# SCH_Trabajo_TEC.net
KiCad netlist of a schematic drawn in EasyEDA
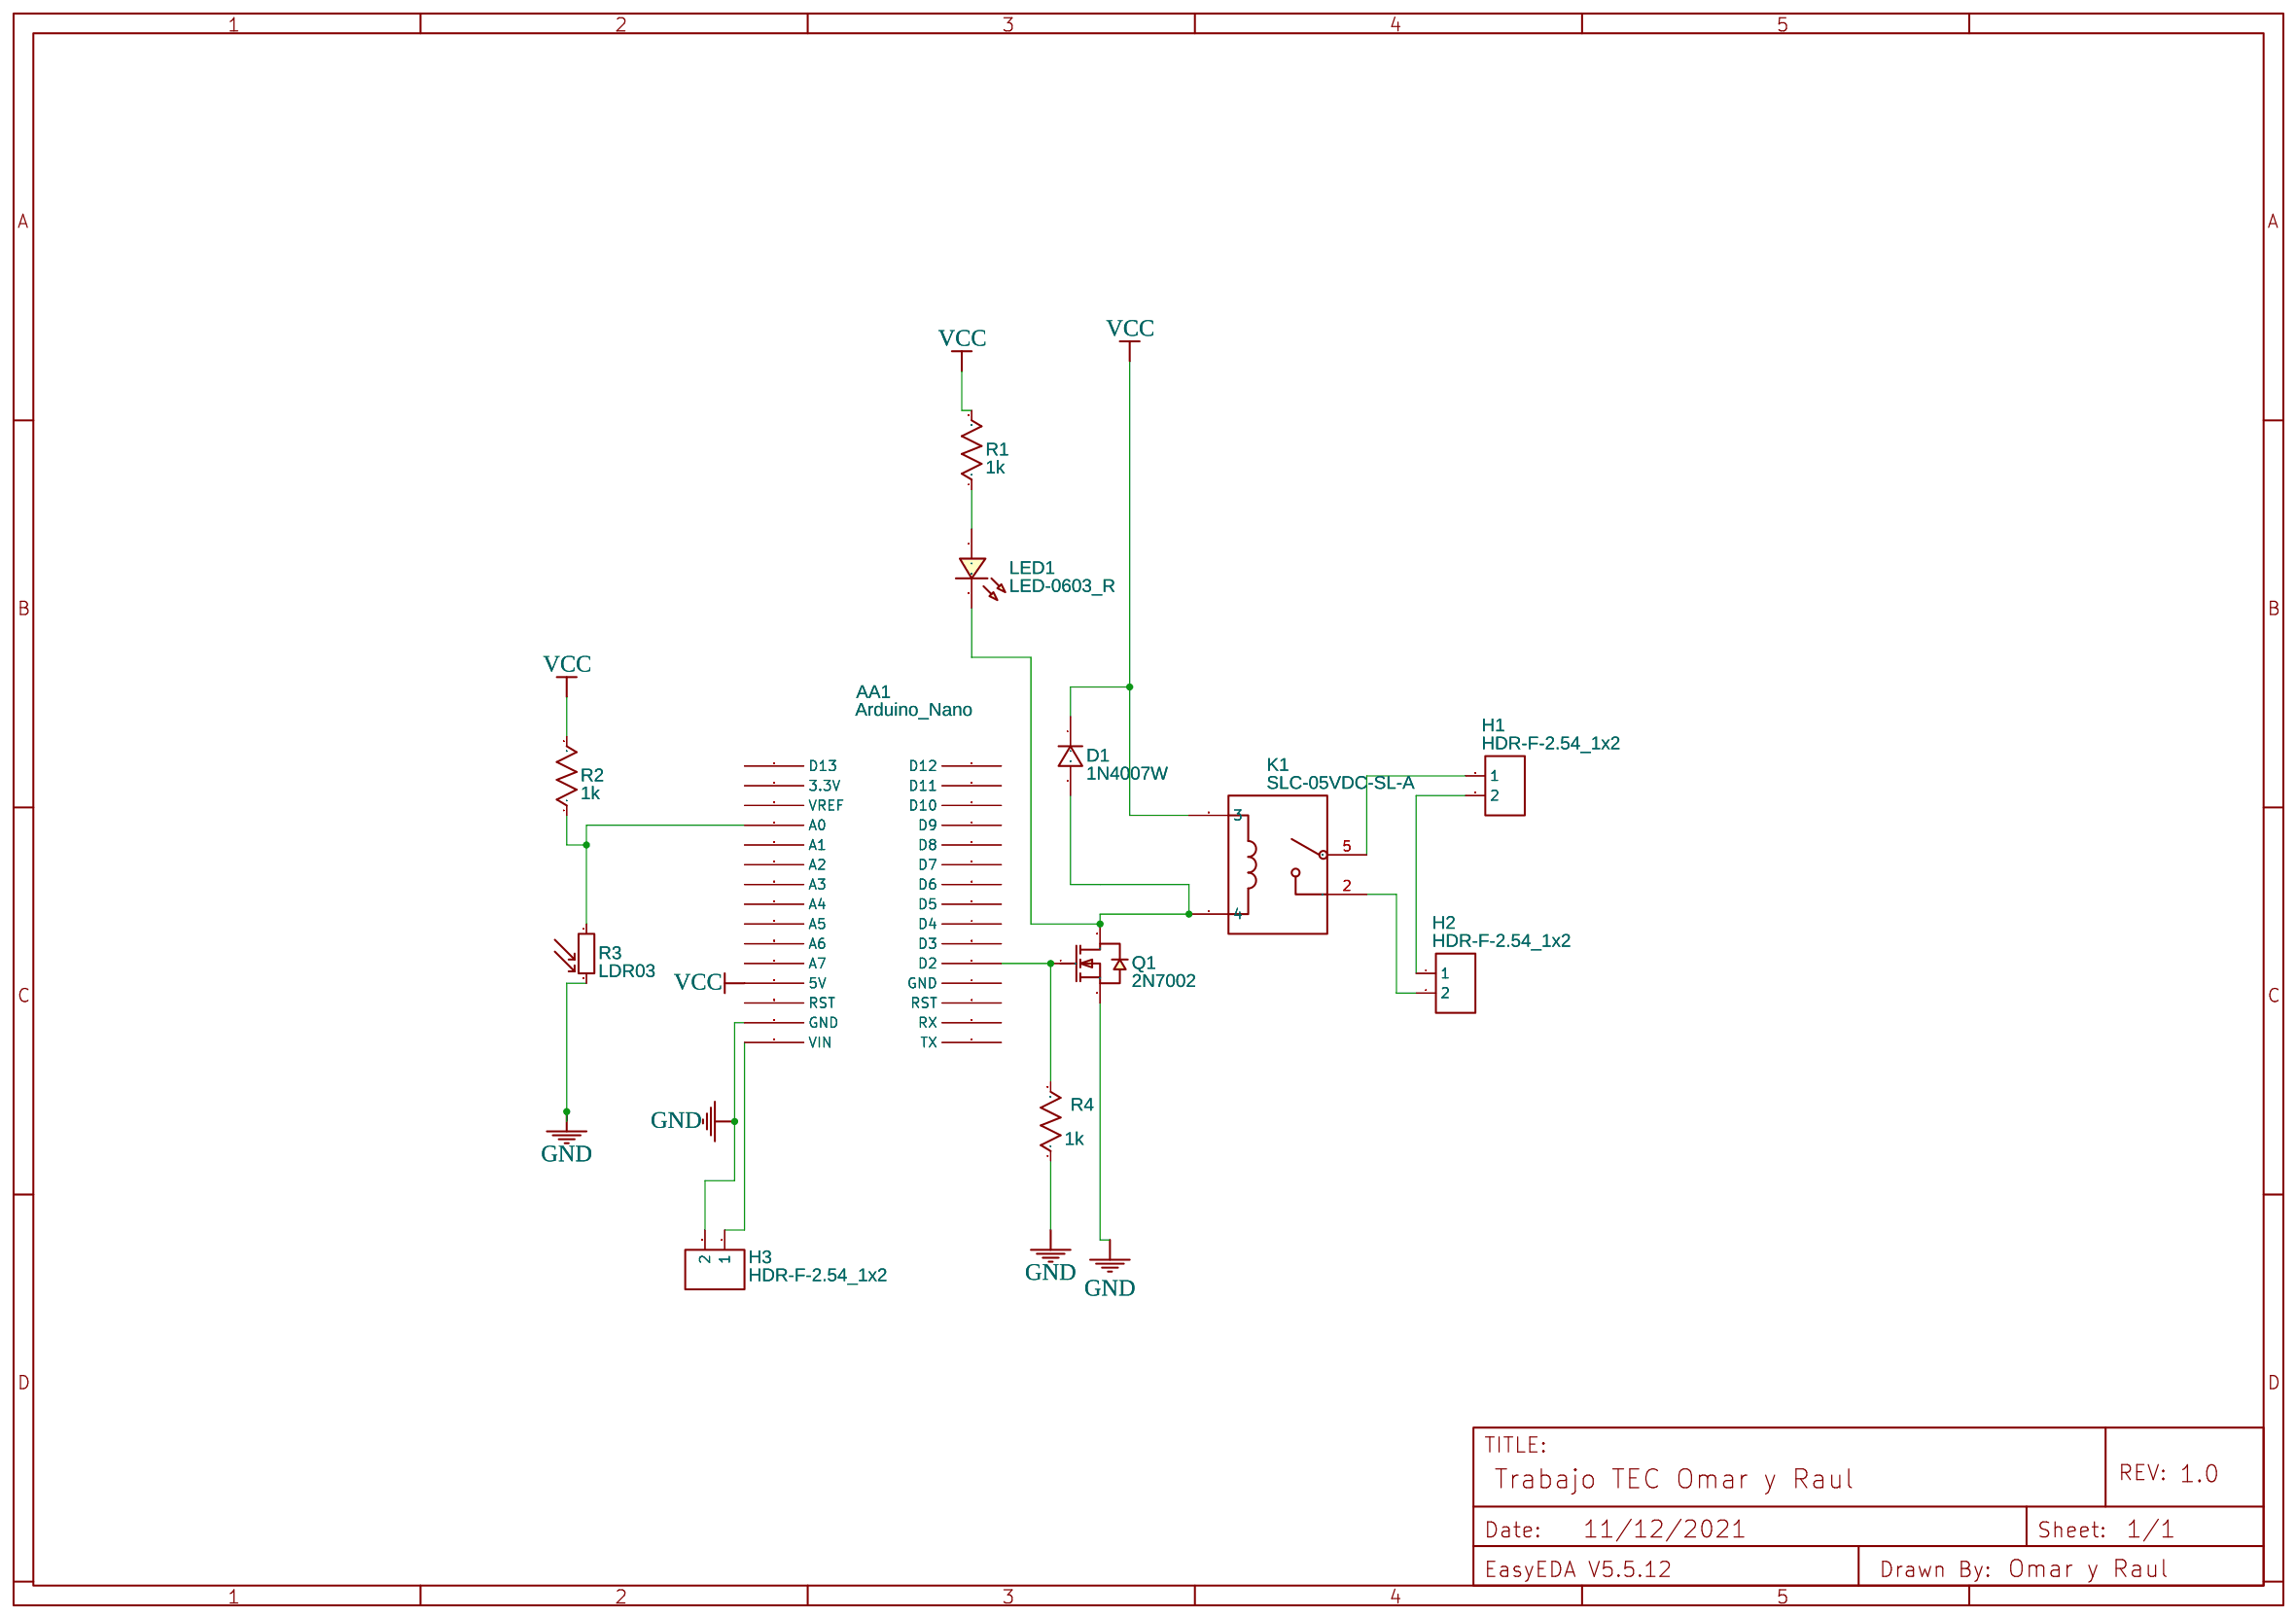
[diagram p0: schematic sheet]

(export (version "E")
  (design (tool "Eeschema 10.0.6"))
  (components
    (comp (ref "AA1")
      (value "Arduino_Nano")
      (fields (field (name "BOM_Manufacturer Part") "Arduino Nano"))
      (libsource (lib "") (part "Unknown_520_-360"))
    )
    (comp (ref "D1")
      (value "1N4007W")
      (fields (field (name "BOM_Supplier Part") "C328592"))
      (libsource (lib "") (part "1N4007W"))
    )
    (comp (ref "H1")
      (value "HDR-F-2.54_1x2")
      (fields (field (name "BOM_Supplier Part") "C49661"))
      (libsource (lib "") (part "HDR-F-2.54_1x2_1"))
    )
    (comp (ref "H2")
      (value "HDR-F-2.54_1x2")
      (fields (field (name "BOM_Supplier Part") "C49661"))
      (libsource (lib "") (part "HDR-F-2.54_1x2_1"))
    )
    (comp (ref "H3")
      (value "HDR-F-2.54_1x2")
      (fields (field (name "BOM_Supplier Part") "C49661"))
      (libsource (lib "") (part "HDR-F-2.54_1x2"))
    )
    (comp (ref "K1")
      (value "SLC-05VDC-SL-A")
      (fields (field (name "BOM_Supplier Part") "C187903"))
      (libsource (lib "") (part "SLC-05VDC-SL-A"))
    )
    (comp (ref "LED1")
      (value "LED-0603_R")
      (fields
        (field (name "BOM_Manufacturer Part") "19-217/R6C-AL1M2VY/3T")
        (field (name "BOM_Supplier Part") "C72044")
      )
      (libsource (lib "") (part "LED-0603_R"))
    )
    (comp (ref "Q1")
      (value "2N7002")
      (fields (field (name "BOM_Manufacturer Part") "2N7002,215") (field (name "BOM_Supplier Part") "C65189"))
      (libsource (lib "") (part "2N7002"))
    )
    (comp (ref "R1") (value "1k") (libsource (lib "") (part "R_0603_US")))
    (comp (ref "R2") (value "1k") (libsource (lib "") (part "R_0603_US")))
    (comp (ref "R3") (value "LDR03") (libsource (lib "") (part "LDR03")))
    (comp (ref "R4") (value "1k") (libsource (lib "") (part "R_0603_US")))
  )
  (nets
    (net (code "1") (name "GND") (class "Default")
      (node (ref "AA1") (pin "29") (pinfunction "GND_29") (pintype "unspecified"))
      (node (ref "H3") (pin "2") (pinfunction "2_2") (pintype "input"))
      (node (ref "Q1") (pin "2") (pinfunction "S_2") (pintype "unspecified"))
      (node (ref "R3") (pin "2") (pintype "unspecified"))
      (node (ref "R4") (pin "1") (pinfunction "1_1") (pintype "unspecified"))
    )
    (net (code "2") (name "Net-(AA1-A0)") (class "Default")
      (node (ref "AA1") (pin "19") (pinfunction "A0_19") (pintype "unspecified"))
      (node (ref "R2") (pin "1") (pinfunction "1_1") (pintype "unspecified"))
      (node (ref "R3") (pin "1") (pintype "unspecified"))
    )
    (net (code "3") (name "Net-(AA1-D2)") (class "Default")
      (node (ref "AA1") (pin "5") (pinfunction "D2_5") (pintype "unspecified"))
      (node (ref "Q1") (pin "1") (pinfunction "G_1") (pintype "unspecified"))
      (node (ref "R4") (pin "2") (pinfunction "2_2") (pintype "unspecified"))
    )
    (net (code "4") (name "Net-(AA1-VIN)") (class "Default")
      (node (ref "AA1") (pin "30") (pinfunction "VIN_30") (pintype "unspecified"))
      (node (ref "H3") (pin "1") (pinfunction "1_1") (pintype "input"))
    )
    (net (code "5") (name "Net-(H1-Pad1)") (class "Default")
      (node (ref "H1") (pin "1") (pinfunction "1_1") (pintype "input"))
      (node (ref "K1") (pin "5") (pinfunction "5_5") (pintype "unspecified"))
    )
    (net (code "6") (name "Net-(H1-Pad2)") (class "Default")
      (node (ref "H1") (pin "2") (pinfunction "2_2") (pintype "input"))
      (node (ref "H2") (pin "1") (pinfunction "1_1") (pintype "input"))
    )
    (net (code "7") (name "Net-(H2-Pad2)") (class "Default")
      (node (ref "H2") (pin "2") (pinfunction "2_2") (pintype "input"))
      (node (ref "K1") (pin "2") (pinfunction "2_2") (pintype "unspecified"))
    )
    (net (code "8") (name "Net-(LED1-Pad1)") (class "Default")
      (node (ref "LED1") (pin "1") (pinfunction "1_1") (pintype "unspecified"))
      (node (ref "R1") (pin "1") (pinfunction "1_1") (pintype "unspecified"))
    )
    (net (code "9") (name "Net-(Q1-D)") (class "Default")
      (node (ref "D1") (pin "2") (pinfunction "2_2") (pintype "unspecified"))
      (node (ref "K1") (pin "4") (pinfunction "4_4") (pintype "unspecified"))
      (node (ref "LED1") (pin "2") (pinfunction "2_2") (pintype "unspecified"))
      (node (ref "Q1") (pin "3") (pinfunction "D_3") (pintype "unspecified"))
    )
    (net (code "10") (name "VCC") (class "Default")
      (node (ref "AA1") (pin "27") (pinfunction "5V_27") (pintype "unspecified"))
      (node (ref "D1") (pin "1") (pinfunction "1_1") (pintype "unspecified"))
      (node (ref "K1") (pin "3") (pinfunction "3_3") (pintype "unspecified"))
      (node (ref "R1") (pin "2") (pinfunction "2_2") (pintype "unspecified"))
      (node (ref "R2") (pin "2") (pinfunction "2_2") (pintype "unspecified"))
    )
    (net (code "11") (name "unconnected-(AA1-3.3V-Pad17)") (class "Default")
      (node (ref "AA1") (pin "17") (pinfunction "3.3V_17") (pintype "unspecified"))
    )
    (net (code "12") (name "unconnected-(AA1-A1-Pad20)") (class "Default")
      (node (ref "AA1") (pin "20") (pinfunction "A1_20") (pintype "unspecified"))
    )
    (net (code "13") (name "unconnected-(AA1-A2-Pad21)") (class "Default")
      (node (ref "AA1") (pin "21") (pinfunction "A2_21") (pintype "unspecified"))
    )
    (net (code "14") (name "unconnected-(AA1-A3-Pad22)") (class "Default")
      (node (ref "AA1") (pin "22") (pinfunction "A3_22") (pintype "unspecified"))
    )
    (net (code "15") (name "unconnected-(AA1-A4-Pad23)") (class "Default")
      (node (ref "AA1") (pin "23") (pinfunction "A4_23") (pintype "unspecified"))
    )
    (net (code "16") (name "unconnected-(AA1-A5-Pad24)") (class "Default")
      (node (ref "AA1") (pin "24") (pinfunction "A5_24") (pintype "unspecified"))
    )
    (net (code "17") (name "unconnected-(AA1-A6-Pad25)") (class "Default")
      (node (ref "AA1") (pin "25") (pinfunction "A6_25") (pintype "unspecified"))
    )
    (net (code "18") (name "unconnected-(AA1-A7-Pad26)") (class "Default")
      (node (ref "AA1") (pin "26") (pinfunction "A7_26") (pintype "unspecified"))
    )
    (net (code "19") (name "unconnected-(AA1-D3-Pad6)") (class "Default")
      (node (ref "AA1") (pin "6") (pinfunction "D3_6") (pintype "unspecified"))
    )
    (net (code "20") (name "unconnected-(AA1-D4-Pad7)") (class "Default")
      (node (ref "AA1") (pin "7") (pinfunction "D4_7") (pintype "unspecified"))
    )
    (net (code "21") (name "unconnected-(AA1-D5-Pad8)") (class "Default")
      (node (ref "AA1") (pin "8") (pinfunction "D5_8") (pintype "unspecified"))
    )
    (net (code "22") (name "unconnected-(AA1-D6-Pad9)") (class "Default")
      (node (ref "AA1") (pin "9") (pinfunction "D6_9") (pintype "unspecified"))
    )
    (net (code "23") (name "unconnected-(AA1-D7-Pad10)") (class "Default")
      (node (ref "AA1") (pin "10") (pinfunction "D7_10") (pintype "unspecified"))
    )
    (net (code "24") (name "unconnected-(AA1-D8-Pad11)") (class "Default")
      (node (ref "AA1") (pin "11") (pinfunction "D8_11") (pintype "unspecified"))
    )
    (net (code "25") (name "unconnected-(AA1-D9-Pad12)") (class "Default")
      (node (ref "AA1") (pin "12") (pinfunction "D9_12") (pintype "unspecified"))
    )
    (net (code "26") (name "unconnected-(AA1-D10-Pad13)") (class "Default")
      (node (ref "AA1") (pin "13") (pinfunction "D10_13") (pintype "unspecified"))
    )
    (net (code "27") (name "unconnected-(AA1-D11-Pad14)") (class "Default")
      (node (ref "AA1") (pin "14") (pinfunction "D11_14") (pintype "unspecified"))
    )
    (net (code "28") (name "unconnected-(AA1-D12-Pad15)") (class "Default")
      (node (ref "AA1") (pin "15") (pinfunction "D12_15") (pintype "unspecified"))
    )
    (net (code "29") (name "unconnected-(AA1-D13-Pad16)") (class "Default")
      (node (ref "AA1") (pin "16") (pinfunction "D13_16") (pintype "unspecified"))
    )
    (net (code "30") (name "unconnected-(AA1-GND-Pad4)") (class "Default")
      (node (ref "AA1") (pin "4") (pinfunction "GND_4") (pintype "unspecified"))
    )
    (net (code "31") (name "unconnected-(AA1-RST-Pad3)") (class "Default")
      (node (ref "AA1") (pin "3") (pinfunction "RST_3") (pintype "unspecified"))
    )
    (net (code "32") (name "unconnected-(AA1-RST-Pad28)") (class "Default")
      (node (ref "AA1") (pin "28") (pinfunction "RST_28") (pintype "unspecified"))
    )
    (net (code "33") (name "unconnected-(AA1-RX-Pad2)") (class "Default")
      (node (ref "AA1") (pin "2") (pinfunction "RX_2") (pintype "unspecified"))
    )
    (net (code "34") (name "unconnected-(AA1-TX-Pad1)") (class "Default")
      (node (ref "AA1") (pin "1") (pinfunction "TX_1") (pintype "unspecified"))
    )
    (net (code "35") (name "unconnected-(AA1-VREF-Pad18)") (class "Default")
      (node (ref "AA1") (pin "18") (pinfunction "VREF_18") (pintype "unspecified"))
    )
  )
)
